# AUDIO.net
KiCad netlist of a schematic drawn in Altium Designer
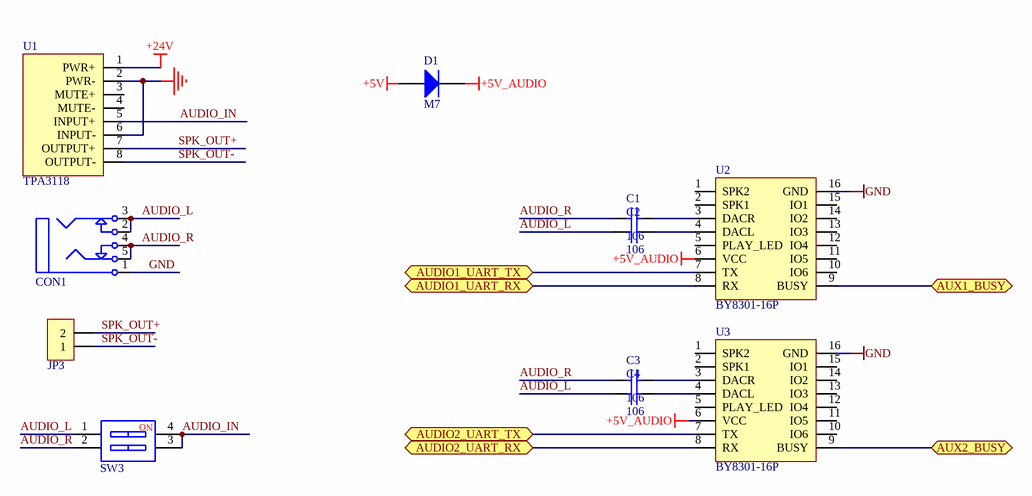
[diagram p0: AUDIO.SchDoc]

(export (version "E")
  (design (tool "Eeschema 10.0.6"))
  (components
    (comp (ref "C1")
      (value "106")
      (footprint "C 1206")
      (description "Capacitor")
      (fields (field (name "PUBLISHER") "Altium Limited"))
      (libsource (lib "Miscellaneous Devices") (part "Cap"))
    )
    (comp (ref "C2")
      (value "106")
      (footprint "C 1206")
      (description "Capacitor")
      (fields (field (name "PUBLISHER") "Altium Limited"))
      (libsource (lib "Miscellaneous Devices") (part "Cap"))
    )
    (comp (ref "C3")
      (value "106")
      (footprint "C 1206")
      (description "Capacitor")
      (fields (field (name "PUBLISHER") "Altium Limited"))
      (libsource (lib "Miscellaneous Devices") (part "Cap"))
    )
    (comp (ref "C4")
      (value "106")
      (footprint "C 1206")
      (description "Capacitor")
      (fields (field (name "PUBLISHER") "Altium Limited"))
      (libsource (lib "Miscellaneous Devices") (part "Cap"))
    )
    (comp (ref "CON1")
      (value "PJ325_BK")
      (footprint "PJ325_PK")
      (description "3.5mm耳机插座")
      (fields (field (name "版权归属") "源创客"))
      (libsource (lib "接口类") (part "PJ325"))
    )
    (comp (ref "D1") (value "M7") (footprint "SMA") (libsource (lib "any") (part "Diode")))
    (comp (ref "JP3")
      (value "AUX")
      (footprint "557-2X1")
      (description "2P接插件")
      (fields (field (name "版权归属") "源创客"))
      (libsource (lib "接插件") (part "Header 2"))
    )
    (comp (ref "SW3")
      (value "CSW-2P")
      (footprint "CSW1.27 SMD-2P")
      (description "2路编码开关")
      (fields (field (name "版权归属") "源创客"))
      (libsource (lib "按键-开关") (part "CSW-2P"))
    )
    (comp (ref "U1")
      (value "TPA3118")
      (footprint "TPA3118-L")
      (description "TPA3118单声道功放板")
      (libsource (lib "模块") (part "TPA3118"))
    )
    (comp (ref "U2")
      (value "BY8301-16P")
      (footprint "BY8301-16P")
      (description "BY8001-16P语音模块")
      (libsource (lib "模块") (part "BY8301-16P"))
    )
    (comp (ref "U3")
      (value "BY8301-16P")
      (footprint "BY8301-16P")
      (description "BY8001-16P语音模块")
      (libsource (lib "模块") (part "BY8301-16P"))
    )
  )
  (nets
    (net (code "1") (name "+5V") (class "Default")
      (node (ref "D1") (pin "1") (pinfunction "1_1") (pintype "passive"))
    )
    (net (code "2") (name "+5V_AUDIO") (class "Default")
      (node (ref "D1") (pin "2") (pinfunction "2_2") (pintype "passive"))
      (node (ref "U2") (pin "6") (pinfunction "VCC_6") (pintype "passive"))
      (node (ref "U3") (pin "6") (pinfunction "VCC_6") (pintype "passive"))
    )
    (net (code "3") (name "+24V") (class "Default")
      (node (ref "U1") (pin "1") (pinfunction "PWR+_1") (pintype "passive"))
    )
    (net (code "4") (name "/AUDIO1_UART_RX") (class "Default")
      (node (ref "U2") (pin "8") (pinfunction "RX_8") (pintype "passive"))
    )
    (net (code "5") (name "/AUDIO1_UART_TX") (class "Default")
      (node (ref "U2") (pin "7") (pinfunction "TX_7") (pintype "passive"))
    )
    (net (code "6") (name "/AUDIO2_UART_RX") (class "Default")
      (node (ref "U3") (pin "8") (pinfunction "RX_8") (pintype "passive"))
    )
    (net (code "7") (name "/AUDIO2_UART_TX") (class "Default")
      (node (ref "U3") (pin "7") (pinfunction "TX_7") (pintype "passive"))
    )
    (net (code "8") (name "/AUDIO_IN") (class "Default")
      (node (ref "SW3") (pin "3") (pinfunction "3_3") (pintype "passive"))
      (node (ref "SW3") (pin "4") (pinfunction "4_4") (pintype "passive"))
      (node (ref "U1") (pin "5") (pinfunction "INPUT+_5") (pintype "passive"))
    )
    (net (code "9") (name "/AUDIO_L") (class "Default")
      (node (ref "C2") (pin "1") (pinfunction "1_1") (pintype "passive"))
      (node (ref "C4") (pin "1") (pinfunction "1_1") (pintype "passive"))
      (node (ref "CON1") (pin "2") (pinfunction "2_2") (pintype "passive"))
      (node (ref "CON1") (pin "3") (pinfunction "3_3") (pintype "passive"))
      (node (ref "SW3") (pin "1") (pinfunction "1_1") (pintype "passive"))
    )
    (net (code "10") (name "/AUDIO_R") (class "Default")
      (node (ref "C1") (pin "1") (pinfunction "1_1") (pintype "passive"))
      (node (ref "C3") (pin "1") (pinfunction "1_1") (pintype "passive"))
      (node (ref "CON1") (pin "4") (pinfunction "4_4") (pintype "passive"))
      (node (ref "CON1") (pin "5") (pinfunction "5_5") (pintype "passive"))
      (node (ref "SW3") (pin "2") (pinfunction "2_2") (pintype "passive"))
    )
    (net (code "11") (name "/AUX1_BUSY") (class "Default")
      (node (ref "U2") (pin "9") (pinfunction "BUSY_9") (pintype "passive"))
    )
    (net (code "12") (name "/AUX2_BUSY") (class "Default")
      (node (ref "U3") (pin "9") (pinfunction "BUSY_9") (pintype "passive"))
    )
    (net (code "13") (name "/SPK_OUT+") (class "Default")
      (node (ref "JP3") (pin "2") (pinfunction "2_2") (pintype "passive"))
      (node (ref "U1") (pin "7") (pinfunction "OUTPUT+_7") (pintype "passive"))
    )
    (net (code "14") (name "/SPK_OUT-") (class "Default")
      (node (ref "JP3") (pin "1") (pinfunction "1_1") (pintype "passive"))
      (node (ref "U1") (pin "8") (pinfunction "OUTPUT-_8") (pintype "passive"))
    )
    (net (code "15") (name "GND") (class "Default")
      (node (ref "CON1") (pin "1") (pinfunction "1_1") (pintype "passive"))
      (node (ref "U1") (pin "2") (pinfunction "PWR-_2") (pintype "passive"))
      (node (ref "U1") (pin "6") (pinfunction "INPUT-_6") (pintype "passive"))
      (node (ref "U2") (pin "16") (pinfunction "GND_16") (pintype "passive"))
      (node (ref "U3") (pin "16") (pinfunction "GND_16") (pintype "passive"))
    )
    (net (code "16") (name "Net-(U2-DACL)") (class "Default")
      (node (ref "C2") (pin "2") (pinfunction "2_2") (pintype "passive"))
      (node (ref "U2") (pin "4") (pinfunction "DACL_4") (pintype "passive"))
    )
    (net (code "17") (name "Net-(U2-DACR)") (class "Default")
      (node (ref "C1") (pin "2") (pinfunction "2_2") (pintype "passive"))
      (node (ref "U2") (pin "3") (pinfunction "DACR_3") (pintype "passive"))
    )
    (net (code "18") (name "Net-(U3-DACL)") (class "Default")
      (node (ref "C4") (pin "2") (pinfunction "2_2") (pintype "passive"))
      (node (ref "U3") (pin "4") (pinfunction "DACL_4") (pintype "passive"))
    )
    (net (code "19") (name "Net-(U3-DACR)") (class "Default")
      (node (ref "C3") (pin "2") (pinfunction "2_2") (pintype "passive"))
      (node (ref "U3") (pin "3") (pinfunction "DACR_3") (pintype "passive"))
    )
    (net (code "20") (name "unconnected-(U1-MUTE+-Pad3)") (class "Default")
      (node (ref "U1") (pin "3") (pinfunction "MUTE+_3") (pintype "passive"))
    )
    (net (code "21") (name "unconnected-(U1-MUTE--Pad4)") (class "Default")
      (node (ref "U1") (pin "4") (pinfunction "MUTE-_4") (pintype "passive"))
    )
    (net (code "22") (name "unconnected-(U2-IO1-Pad15)") (class "Default")
      (node (ref "U2") (pin "15") (pinfunction "IO1_15") (pintype "passive"))
    )
    (net (code "23") (name "unconnected-(U2-IO2-Pad14)") (class "Default")
      (node (ref "U2") (pin "14") (pinfunction "IO2_14") (pintype "passive"))
    )
    (net (code "24") (name "unconnected-(U2-IO3-Pad13)") (class "Default")
      (node (ref "U2") (pin "13") (pinfunction "IO3_13") (pintype "passive"))
    )
    (net (code "25") (name "unconnected-(U2-IO4-Pad12)") (class "Default")
      (node (ref "U2") (pin "12") (pinfunction "IO4_12") (pintype "passive"))
    )
    (net (code "26") (name "unconnected-(U2-IO5-Pad11)") (class "Default")
      (node (ref "U2") (pin "11") (pinfunction "IO5_11") (pintype "passive"))
    )
    (net (code "27") (name "unconnected-(U2-IO6-Pad10)") (class "Default")
      (node (ref "U2") (pin "10") (pinfunction "IO6_10") (pintype "passive"))
    )
    (net (code "28") (name "unconnected-(U2-PLAY_LED-Pad5)") (class "Default")
      (node (ref "U2") (pin "5") (pinfunction "PLAY_LED_5") (pintype "passive"))
    )
    (net (code "29") (name "unconnected-(U2-SPK1-Pad2)") (class "Default")
      (node (ref "U2") (pin "2") (pinfunction "SPK1_2") (pintype "passive"))
    )
    (net (code "30") (name "unconnected-(U2-SPK2-Pad1)") (class "Default")
      (node (ref "U2") (pin "1") (pinfunction "SPK2_1") (pintype "passive"))
    )
    (net (code "31") (name "unconnected-(U3-IO1-Pad15)") (class "Default")
      (node (ref "U3") (pin "15") (pinfunction "IO1_15") (pintype "passive"))
    )
    (net (code "32") (name "unconnected-(U3-IO2-Pad14)") (class "Default")
      (node (ref "U3") (pin "14") (pinfunction "IO2_14") (pintype "passive"))
    )
    (net (code "33") (name "unconnected-(U3-IO3-Pad13)") (class "Default")
      (node (ref "U3") (pin "13") (pinfunction "IO3_13") (pintype "passive"))
    )
    (net (code "34") (name "unconnected-(U3-IO4-Pad12)") (class "Default")
      (node (ref "U3") (pin "12") (pinfunction "IO4_12") (pintype "passive"))
    )
    (net (code "35") (name "unconnected-(U3-IO5-Pad11)") (class "Default")
      (node (ref "U3") (pin "11") (pinfunction "IO5_11") (pintype "passive"))
    )
    (net (code "36") (name "unconnected-(U3-IO6-Pad10)") (class "Default")
      (node (ref "U3") (pin "10") (pinfunction "IO6_10") (pintype "passive"))
    )
    (net (code "37") (name "unconnected-(U3-PLAY_LED-Pad5)") (class "Default")
      (node (ref "U3") (pin "5") (pinfunction "PLAY_LED_5") (pintype "passive"))
    )
    (net (code "38") (name "unconnected-(U3-SPK1-Pad2)") (class "Default")
      (node (ref "U3") (pin "2") (pinfunction "SPK1_2") (pintype "passive"))
    )
    (net (code "39") (name "unconnected-(U3-SPK2-Pad1)") (class "Default")
      (node (ref "U3") (pin "1") (pinfunction "SPK2_1") (pintype "passive"))
    )
  )
)
